# General_Overview.net
KiCad netlist of a schematic drawn in Altium Designer
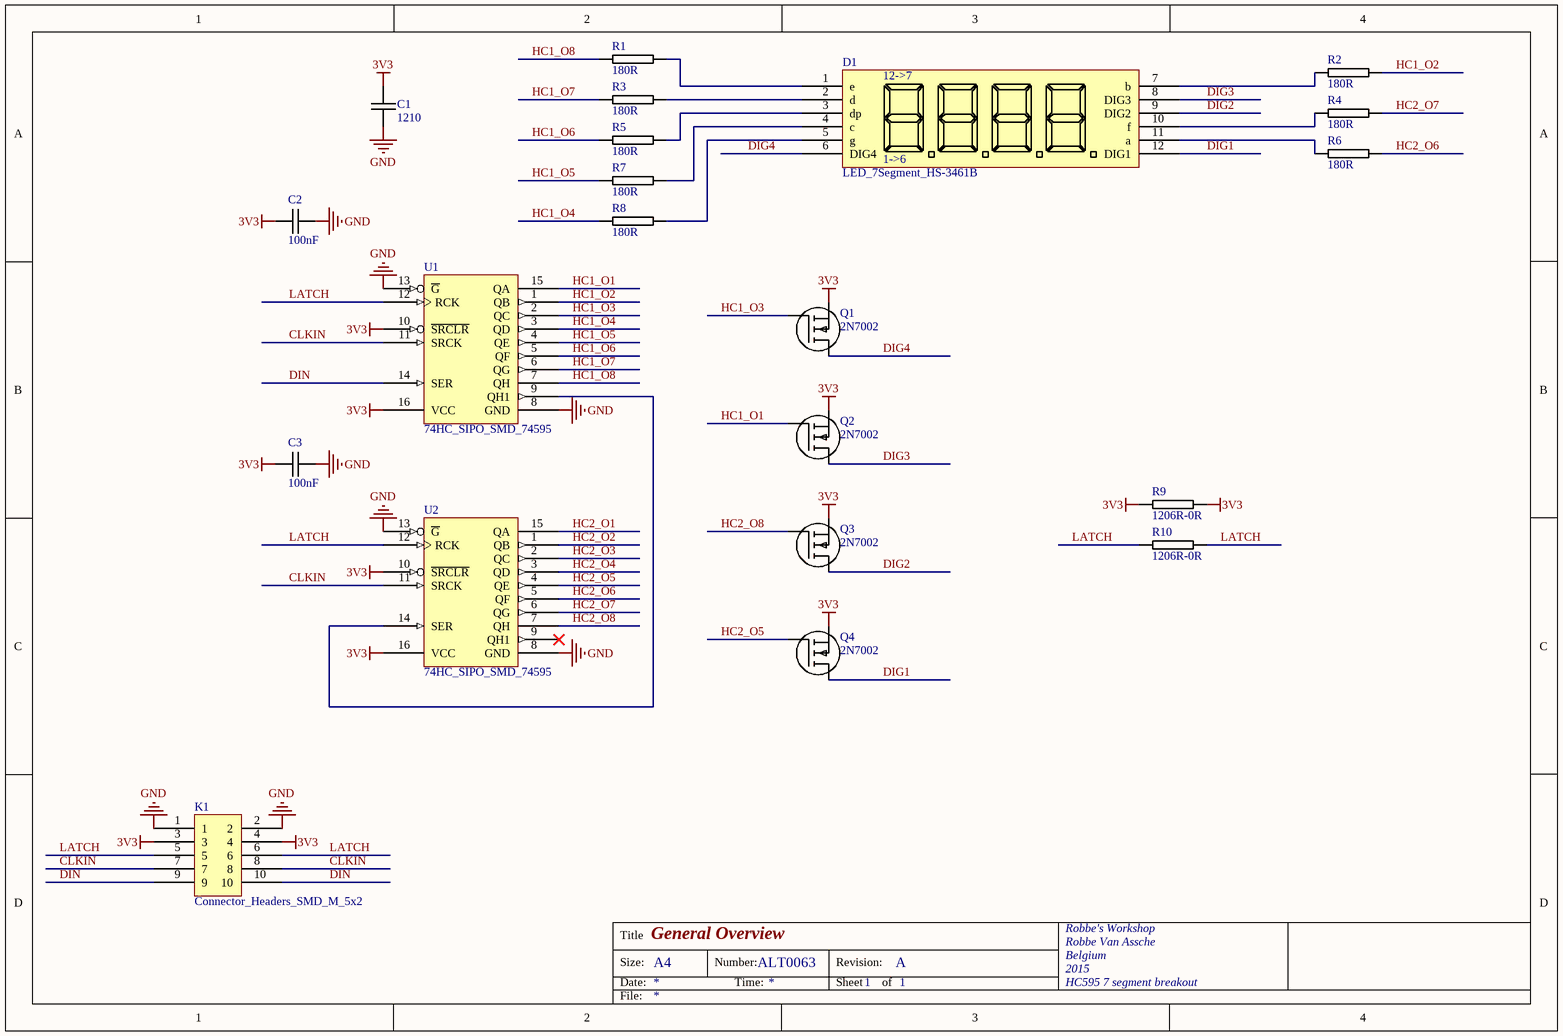
[diagram p0: General Overview.SchDoc]

(export (version "E")
  (design (tool "Eeschema 10.0.6"))
  (components
    (comp (ref "C1")
      (value "1210")
      (footprint "1210C-GENERIC")
      (description "CAPACITOR 1210 CERAMIC VALUE TO BE DETERMINED")
      (libsource (lib "RVA_Altium_Library") (part "Passives_Capacitors_1210_1210C-TBD"))
    )
    (comp (ref "C2")
      (value "100nF")
      (footprint "0805C-TBD")
      (description "CAPACITOR 0805 CERAMIC")
      (libsource (lib "RVA_Altium_Library") (part "Passives_Capacitors_0805_100nF-25V-X7R-MUR"))
    )
    (comp (ref "C3")
      (value "100nF")
      (footprint "0805C-TBD")
      (description "CAPACITOR 0805 CERAMIC")
      (libsource (lib "RVA_Altium_Library") (part "Passives_Capacitors_0805_100nF-25V-X7R-MUR"))
    )
    (comp (ref "D1")
      (value "LED_7Segment_HS-3461B")
      (footprint "HS3461")
      (libsource (lib "RVA_Altium_Library") (part "LED_7Segment_HS-3461B"))
    )
    (comp (ref "K1")
      (value "Connector_Headers_SMD_M_5x2")
      (footprint "Header_Male_2.54 5x2")
      (description "SMD Header 5x2")
      (libsource (lib "RVA_Altium_Library") (part "Connector_Headers_SMD_M_5x2"))
    )
    (comp (ref "Q1")
      (value "2N7002")
      (footprint "SOT23-GDS")
      (description "N CHANNEL MOSFET 2N7002 SOT23")
      (fields (field (name "MANUFACTURER") "Fairchild Semiconductor"))
      (libsource (lib "RVA_Altium_Library") (part "2N7002-SOT23"))
    )
    (comp (ref "Q2")
      (value "2N7002")
      (footprint "SOT23-GDS")
      (description "N CHANNEL MOSFET 2N7002 SOT23")
      (fields (field (name "MANUFACTURER") "Fairchild Semiconductor"))
      (libsource (lib "RVA_Altium_Library") (part "2N7002-SOT23"))
    )
    (comp (ref "Q3")
      (value "2N7002")
      (footprint "SOT23-GDS")
      (description "N CHANNEL MOSFET 2N7002 SOT23")
      (fields (field (name "MANUFACTURER") "Fairchild Semiconductor"))
      (libsource (lib "RVA_Altium_Library") (part "2N7002-SOT23"))
    )
    (comp (ref "Q4")
      (value "2N7002")
      (footprint "SOT23-GDS")
      (description "N CHANNEL MOSFET 2N7002 SOT23")
      (fields (field (name "MANUFACTURER") "Fairchild Semiconductor"))
      (libsource (lib "RVA_Altium_Library") (part "2N7002-SOT23"))
    )
    (comp (ref "R1")
      (value "180R")
      (footprint "0805R-180")
      (description "RESISTOR 0805 1/4 WATT THIN FILM")
      (libsource (lib "RVA_Altium_Library") (part "0805R-180"))
    )
    (comp (ref "R2")
      (value "180R")
      (footprint "0805R-180")
      (description "RESISTOR 0805 1/4 WATT THIN FILM")
      (libsource (lib "RVA_Altium_Library") (part "0805R-180"))
    )
    (comp (ref "R3")
      (value "180R")
      (footprint "0805R-180")
      (description "RESISTOR 0805 1/4 WATT THIN FILM")
      (libsource (lib "RVA_Altium_Library") (part "0805R-180"))
    )
    (comp (ref "R4")
      (value "180R")
      (footprint "0805R-180")
      (description "RESISTOR 0805 1/4 WATT THIN FILM")
      (libsource (lib "RVA_Altium_Library") (part "0805R-180"))
    )
    (comp (ref "R5")
      (value "180R")
      (footprint "0805R-180")
      (description "RESISTOR 0805 1/4 WATT THIN FILM")
      (libsource (lib "RVA_Altium_Library") (part "0805R-180"))
    )
    (comp (ref "R6")
      (value "180R")
      (footprint "0805R-180")
      (description "RESISTOR 0805 1/4 WATT THIN FILM")
      (libsource (lib "RVA_Altium_Library") (part "0805R-180"))
    )
    (comp (ref "R7")
      (value "180R")
      (footprint "0805R-180")
      (description "RESISTOR 0805 1/4 WATT THIN FILM")
      (libsource (lib "RVA_Altium_Library") (part "0805R-180"))
    )
    (comp (ref "R8")
      (value "180R")
      (footprint "0805R-180")
      (description "RESISTOR 0805 1/4 WATT THIN FILM")
      (libsource (lib "RVA_Altium_Library") (part "0805R-180"))
    )
    (comp (ref "R9")
      (value "1206R-0R")
      (footprint "1206R-GENERIC")
      (libsource (lib "RVA_Altium_Library") (part "1206R-0R"))
    )
    (comp (ref "R10")
      (value "1206R-0R")
      (footprint "1206R-GENERIC")
      (libsource (lib "RVA_Altium_Library") (part "1206R-0R"))
    )
    (comp (ref "U1")
      (value "74HC_SIPO_SMD_74595")
      (footprint "SO16")
      (description "8-BIT SFT REG WIRTH OUTPUT LCH")
      (libsource (lib "RVA_Altium_Library") (part "74HC_SIPO_SMD_74595"))
    )
    (comp (ref "U2")
      (value "74HC_SIPO_SMD_74595")
      (footprint "SO16")
      (description "8-BIT SFT REG WIRTH OUTPUT LCH")
      (libsource (lib "RVA_Altium_Library") (part "74HC_SIPO_SMD_74595"))
    )
  )
  (nets
    (net (code "1") (name "/CLKIN") (class "Default")
      (node (ref "K1") (pin "7") (pinfunction "7_7") (pintype "passive"))
      (node (ref "K1") (pin "8") (pinfunction "8_8") (pintype "passive"))
      (node (ref "U1") (pin "11") (pinfunction "SRCK_11") (pintype "input"))
      (node (ref "U2") (pin "11") (pinfunction "SRCK_11") (pintype "input"))
    )
    (net (code "2") (name "/DIG1") (class "Default")
      (node (ref "D1") (pin "12") (pinfunction "DIG1_12") (pintype "passive"))
      (node (ref "Q4") (pin "D") (pintype "passive"))
    )
    (net (code "3") (name "/DIG2") (class "Default")
      (node (ref "D1") (pin "9") (pinfunction "DIG2_9") (pintype "passive"))
      (node (ref "Q3") (pin "D") (pintype "passive"))
    )
    (net (code "4") (name "/DIG3") (class "Default")
      (node (ref "D1") (pin "8") (pinfunction "DIG3_8") (pintype "passive"))
      (node (ref "Q2") (pin "D") (pintype "passive"))
    )
    (net (code "5") (name "/DIG4") (class "Default")
      (node (ref "D1") (pin "6") (pinfunction "DIG4_6") (pintype "passive"))
      (node (ref "Q1") (pin "D") (pintype "passive"))
    )
    (net (code "6") (name "/DIN") (class "Default")
      (node (ref "K1") (pin "10") (pinfunction "10_10") (pintype "passive"))
      (node (ref "K1") (pin "9") (pinfunction "9_9") (pintype "passive"))
      (node (ref "U1") (pin "14") (pinfunction "SER_14") (pintype "input"))
    )
    (net (code "7") (name "/HC1_O1") (class "Default")
      (node (ref "Q2") (pin "G") (pintype "passive"))
      (node (ref "U1") (pin "15") (pinfunction "QA_15") (pintype "tri_state"))
    )
    (net (code "8") (name "/HC1_O2") (class "Default")
      (node (ref "R2") (pin "2") (pintype "passive"))
      (node (ref "U1") (pin "1") (pinfunction "QB_1") (pintype "output"))
    )
    (net (code "9") (name "/HC1_O3") (class "Default")
      (node (ref "Q1") (pin "G") (pintype "passive"))
      (node (ref "U1") (pin "2") (pinfunction "QC_2") (pintype "output"))
    )
    (net (code "10") (name "/HC1_O4") (class "Default")
      (node (ref "R8") (pin "1") (pintype "passive"))
      (node (ref "U1") (pin "3") (pinfunction "QD_3") (pintype "output"))
    )
    (net (code "11") (name "/HC1_O5") (class "Default")
      (node (ref "R7") (pin "1") (pintype "passive"))
      (node (ref "U1") (pin "4") (pinfunction "QE_4") (pintype "output"))
    )
    (net (code "12") (name "/HC1_O6") (class "Default")
      (node (ref "R5") (pin "1") (pintype "passive"))
      (node (ref "U1") (pin "5") (pinfunction "QF_5") (pintype "output"))
    )
    (net (code "13") (name "/HC1_O7") (class "Default")
      (node (ref "R3") (pin "1") (pintype "passive"))
      (node (ref "U1") (pin "6") (pinfunction "QG_6") (pintype "output"))
    )
    (net (code "14") (name "/HC1_O8") (class "Default")
      (node (ref "R1") (pin "1") (pintype "passive"))
      (node (ref "U1") (pin "7") (pinfunction "QH_7") (pintype "tri_state"))
    )
    (net (code "15") (name "/HC2_O1") (class "Default")
      (node (ref "U2") (pin "15") (pinfunction "QA_15") (pintype "tri_state"))
    )
    (net (code "16") (name "/HC2_O2") (class "Default")
      (node (ref "U2") (pin "1") (pinfunction "QB_1") (pintype "output"))
    )
    (net (code "17") (name "/HC2_O3") (class "Default")
      (node (ref "U2") (pin "2") (pinfunction "QC_2") (pintype "output"))
    )
    (net (code "18") (name "/HC2_O4") (class "Default")
      (node (ref "U2") (pin "3") (pinfunction "QD_3") (pintype "output"))
    )
    (net (code "19") (name "/HC2_O5") (class "Default")
      (node (ref "Q4") (pin "G") (pintype "passive"))
      (node (ref "U2") (pin "4") (pinfunction "QE_4") (pintype "output"))
    )
    (net (code "20") (name "/HC2_O6") (class "Default")
      (node (ref "R6") (pin "2") (pintype "passive"))
      (node (ref "U2") (pin "5") (pinfunction "QF_5") (pintype "output"))
    )
    (net (code "21") (name "/HC2_O7") (class "Default")
      (node (ref "R4") (pin "2") (pintype "passive"))
      (node (ref "U2") (pin "6") (pinfunction "QG_6") (pintype "output"))
    )
    (net (code "22") (name "/HC2_O8") (class "Default")
      (node (ref "Q3") (pin "G") (pintype "passive"))
      (node (ref "U2") (pin "7") (pinfunction "QH_7") (pintype "tri_state"))
    )
    (net (code "23") (name "/LATCH") (class "Default")
      (node (ref "K1") (pin "5") (pinfunction "5_5") (pintype "passive"))
      (node (ref "K1") (pin "6") (pinfunction "6_6") (pintype "passive"))
      (node (ref "R10") (pin "1") (pintype "passive"))
      (node (ref "R10") (pin "2") (pintype "passive"))
      (node (ref "U1") (pin "12") (pinfunction "RCK_12") (pintype "input"))
      (node (ref "U2") (pin "12") (pinfunction "RCK_12") (pintype "input"))
    )
    (net (code "24") (name "3V3") (class "Default")
      (node (ref "C1") (pin "1") (pintype "passive"))
      (node (ref "C2") (pin "1") (pintype "passive"))
      (node (ref "C3") (pin "1") (pintype "passive"))
      (node (ref "K1") (pin "3") (pinfunction "3_3") (pintype "passive"))
      (node (ref "K1") (pin "4") (pinfunction "4_4") (pintype "passive"))
      (node (ref "Q1") (pin "S") (pintype "passive"))
      (node (ref "Q2") (pin "S") (pintype "passive"))
      (node (ref "Q3") (pin "S") (pintype "passive"))
      (node (ref "Q4") (pin "S") (pintype "passive"))
      (node (ref "R9") (pin "1") (pintype "passive"))
      (node (ref "R9") (pin "2") (pintype "passive"))
      (node (ref "U1") (pin "10") (pinfunction "~{SRCLR}_10") (pintype "input"))
      (node (ref "U1") (pin "16") (pinfunction "VCC_16") (pintype "power_in"))
      (node (ref "U2") (pin "10") (pinfunction "~{SRCLR}_10") (pintype "input"))
      (node (ref "U2") (pin "16") (pinfunction "VCC_16") (pintype "power_in"))
    )
    (net (code "25") (name "GND") (class "Default")
      (node (ref "C1") (pin "2") (pintype "passive"))
      (node (ref "C2") (pin "2") (pintype "passive"))
      (node (ref "C3") (pin "2") (pintype "passive"))
      (node (ref "K1") (pin "1") (pinfunction "1_1") (pintype "passive"))
      (node (ref "K1") (pin "2") (pinfunction "2_2") (pintype "passive"))
      (node (ref "U1") (pin "13") (pinfunction "~{G}_13") (pintype "input"))
      (node (ref "U1") (pin "8") (pinfunction "GND_8") (pintype "power_in"))
      (node (ref "U2") (pin "13") (pinfunction "~{G}_13") (pintype "input"))
      (node (ref "U2") (pin "8") (pinfunction "GND_8") (pintype "power_in"))
    )
    (net (code "26") (name "Net-(D1-a)") (class "Default")
      (node (ref "D1") (pin "11") (pinfunction "a_11") (pintype "passive"))
      (node (ref "R6") (pin "1") (pintype "passive"))
    )
    (net (code "27") (name "Net-(D1-b)") (class "Default")
      (node (ref "D1") (pin "7") (pinfunction "b_7") (pintype "passive"))
      (node (ref "R2") (pin "1") (pintype "passive"))
    )
    (net (code "28") (name "Net-(D1-c)") (class "Default")
      (node (ref "D1") (pin "4") (pinfunction "c_4") (pintype "passive"))
      (node (ref "R7") (pin "2") (pintype "passive"))
    )
    (net (code "29") (name "Net-(D1-d)") (class "Default")
      (node (ref "D1") (pin "2") (pinfunction "d_2") (pintype "passive"))
      (node (ref "R3") (pin "2") (pintype "passive"))
    )
    (net (code "30") (name "Net-(D1-dp)") (class "Default")
      (node (ref "D1") (pin "3") (pinfunction "dp_3") (pintype "passive"))
      (node (ref "R5") (pin "2") (pintype "passive"))
    )
    (net (code "31") (name "Net-(D1-e)") (class "Default")
      (node (ref "D1") (pin "1") (pinfunction "e_1") (pintype "passive"))
      (node (ref "R1") (pin "2") (pintype "passive"))
    )
    (net (code "32") (name "Net-(D1-f)") (class "Default")
      (node (ref "D1") (pin "10") (pinfunction "f_10") (pintype "passive"))
      (node (ref "R4") (pin "1") (pintype "passive"))
    )
    (net (code "33") (name "Net-(D1-g)") (class "Default")
      (node (ref "D1") (pin "5") (pinfunction "g_5") (pintype "passive"))
      (node (ref "R8") (pin "2") (pintype "passive"))
    )
    (net (code "34") (name "Net-(U1-QH1)") (class "Default")
      (node (ref "U1") (pin "9") (pinfunction "QH1_9") (pintype "output"))
      (node (ref "U2") (pin "14") (pinfunction "SER_14") (pintype "input"))
    )
    (net (code "35") (name "unconnected-(U2-QH1-Pad9)") (class "Default")
      (node (ref "U2") (pin "9") (pinfunction "QH1_9") (pintype "output+no_connect"))
    )
  )
)
